# boxer_supply.net
KiCad netlist of a schematic drawn in Altium Designer
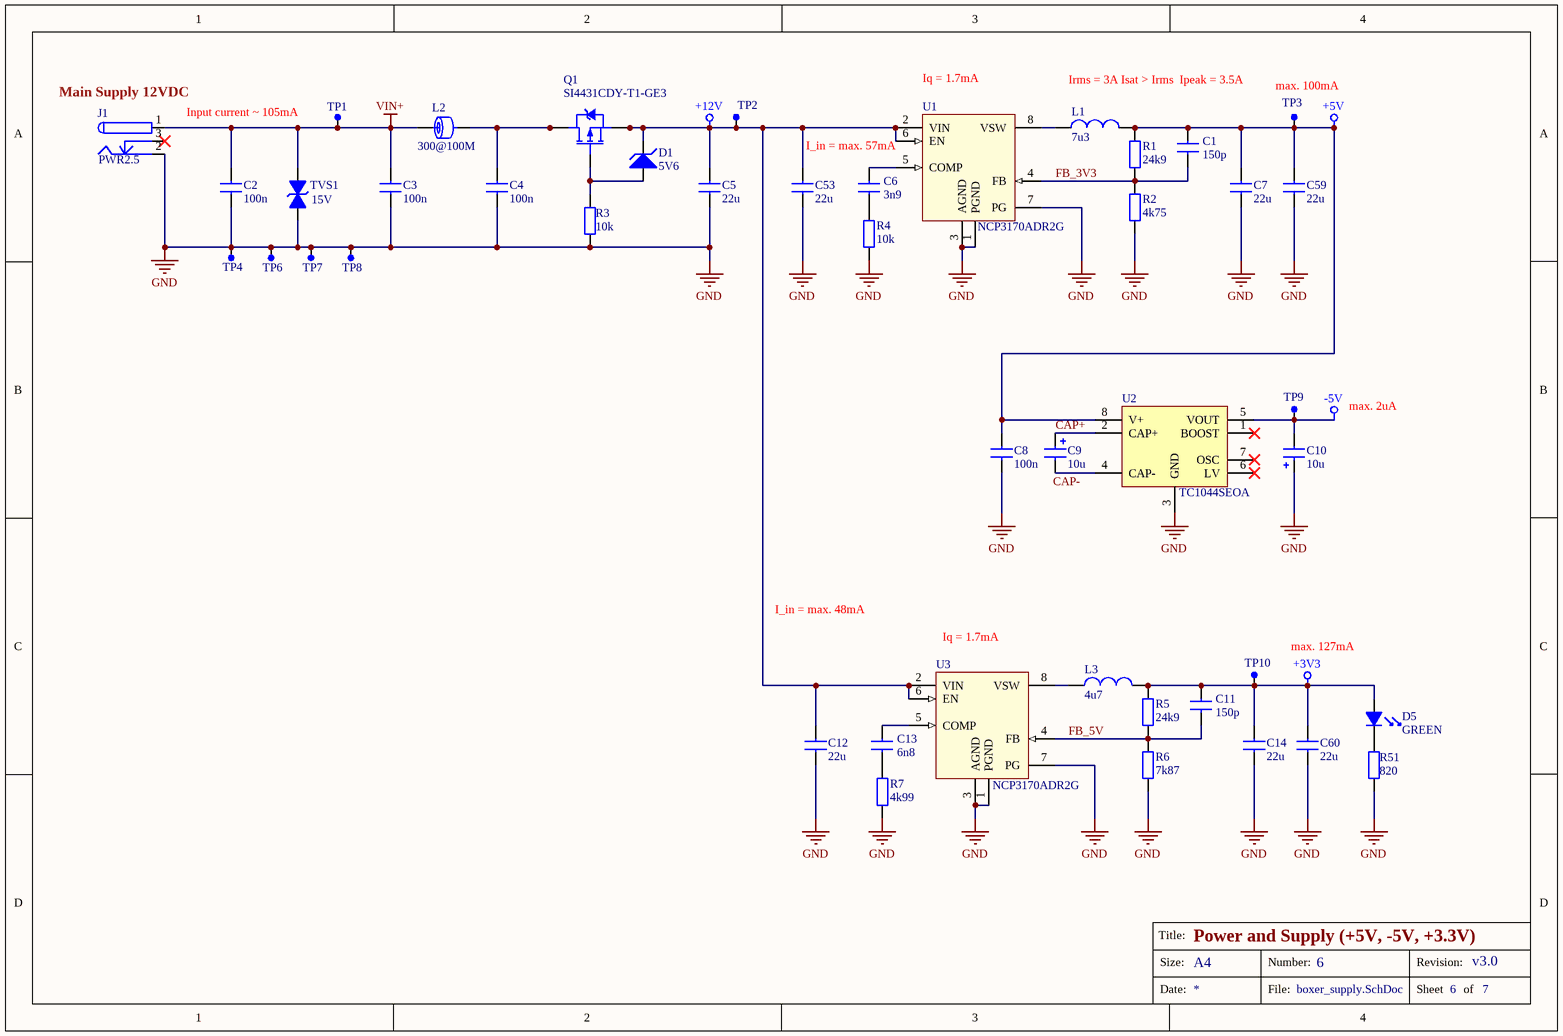
[diagram p0: boxer_supply.SchDoc]

(export (version "E")
  (design (tool "Eeschema 10.0.6"))
  (components
    (comp (ref "C1")
      (value "150p")
      (footprint "C_0805")
      (description "Capacitor")
      (fields (field (name "Comment") "885012207081"))
      (libsource (lib "boxer_pas") (part "Capacitor"))
    )
    (comp (ref "C2")
      (value "100n")
      (footprint "C_0805")
      (description "Capacitor")
      (libsource (lib "boxer_pas") (part "Capacitor"))
    )
    (comp (ref "C3")
      (value "100n")
      (footprint "C_0805")
      (description "Capacitor")
      (libsource (lib "boxer_pas") (part "Capacitor"))
    )
    (comp (ref "C4")
      (value "100n")
      (footprint "C_0805")
      (description "Capacitor")
      (libsource (lib "boxer_pas") (part "Capacitor"))
    )
    (comp (ref "C5")
      (value "22u")
      (footprint "C_1206")
      (description "Capacitor")
      (fields (field (name "Comment") "TME: CL31A226MOCLNNC"))
      (libsource (lib "boxer_pas") (part "Capacitor"))
    )
    (comp (ref "C6")
      (value "3n9")
      (footprint "C_0805")
      (description "Capacitor")
      (fields (field (name "Comment") "885012207089"))
      (libsource (lib "boxer_pas") (part "Capacitor"))
    )
    (comp (ref "C7")
      (value "22u")
      (footprint "C_1206")
      (description "Capacitor")
      (fields (field (name "Comment") "TME: CL31A226MOCLNNC"))
      (libsource (lib "boxer_pas") (part "Capacitor"))
    )
    (comp (ref "C8")
      (value "100n")
      (footprint "C_0805")
      (description "Capacitor")
      (libsource (lib "boxer_pas") (part "Capacitor"))
    )
    (comp (ref "C9")
      (value "10u")
      (footprint "C_SMC")
      (description "Polarized Capacitor")
      (fields (field (name "Comment") "TAJC106K016R"))
      (libsource (lib "boxer_pas") (part "Capacitor Polar"))
    )
    (comp (ref "C10")
      (value "10u")
      (footprint "C_SMC")
      (description "Polarized Capacitor")
      (fields (field (name "Comment") "TAJC106K016R"))
      (libsource (lib "boxer_pas") (part "Capacitor Polar"))
    )
    (comp (ref "C11")
      (value "150p")
      (footprint "C_0805")
      (description "Capacitor")
      (fields (field (name "Comment") "885012207081"))
      (libsource (lib "boxer_pas") (part "Capacitor"))
    )
    (comp (ref "C12")
      (value "22u")
      (footprint "C_1206")
      (description "Capacitor")
      (fields (field (name "Comment") "TME: CL31A226MOCLNNC"))
      (libsource (lib "boxer_pas") (part "Capacitor"))
    )
    (comp (ref "C13")
      (value "6n8")
      (footprint "C_0805")
      (description "Capacitor")
      (fields (field (name "Comment") "885012207091"))
      (libsource (lib "boxer_pas") (part "Capacitor"))
    )
    (comp (ref "C14")
      (value "22u")
      (footprint "C_1206")
      (description "Capacitor")
      (fields (field (name "Comment") "TME: CL31A226MOCLNNC"))
      (libsource (lib "boxer_pas") (part "Capacitor"))
    )
    (comp (ref "C53")
      (value "22u")
      (footprint "C_1206")
      (description "Capacitor")
      (fields (field (name "Comment") "TME: CL31A226MOCLNNC"))
      (libsource (lib "boxer_pas") (part "Capacitor"))
    )
    (comp (ref "C59")
      (value "22u")
      (footprint "C_1206")
      (description "Capacitor")
      (fields (field (name "Comment") "TME: CL31A226MOCLNNC"))
      (libsource (lib "boxer_pas") (part "Capacitor"))
    )
    (comp (ref "C60")
      (value "22u")
      (footprint "C_1206")
      (description "Capacitor")
      (fields (field (name "Comment") "TME: CL31A226MOCLNNC"))
      (libsource (lib "boxer_pas") (part "Capacitor"))
    )
    (comp (ref "D1")
      (value "5V6")
      (footprint "D_SMA")
      (description "Zener Diode")
      (fields (field (name "Comment") "MM3Z5V6B"))
      (libsource (lib "boxer_pas") (part "Diode Zener"))
    )
    (comp (ref "D5")
      (value "GREEN")
      (footprint "LED_0805")
      (description "Typical RED, GREEN, YELLOW, AMBER GaAs LED")
      (fields (field (name "Comment") "KP-2012LSGC"))
      (libsource (lib "altium-import") (part "root_3_LED_"))
    )
    (comp (ref "J1")
      (value "PWR2.5")
      (footprint "WE_WR_DC_694106301002")
      (description "Low Voltage Power Supply Connector")
      (libsource (lib "boxer_mechanical") (part "PWR2.5"))
    )
    (comp (ref "L1")
      (value "7u3")
      (footprint "L_6.7x6.7mm")
      (description "FIXED IND 7.3UH 2.1A 54 MOHM SMD")
      (fields (field (name "Comment") "308-1500-1-ND"))
      (libsource (lib "boxer_pas") (part "Inductor"))
    )
    (comp (ref "L2")
      (value "300@100M")
      (footprint "L_0805")
      (description "Ferrite Bead")
      (fields (field (name "Comment") "742792031"))
      (libsource (lib "boxer_pas") (part "FB"))
    )
    (comp (ref "L3")
      (value "4u7")
      (footprint "L_3.8x3.8mm")
      (description "FIXED IND 4.7UH 1.2A 105 MOHM")
      (fields (field (name "Comment") "732-1008-1-ND"))
      (libsource (lib "boxer_pas") (part "Inductor"))
    )
    (comp (ref "Q1")
      (value "SI4431CDY-T1-GE3")
      (footprint "SO8")
      (description "P-Channel MOSFET")
      (libsource (lib "boxer_pas") (part "MOSFET-P_SO8"))
    )
    (comp (ref "R1")
      (value "24k9")
      (footprint "R_0805")
      (description "Resistor")
      (fields (field (name "Comment") "RNCP0805FTD24K9"))
      (libsource (lib "boxer_pas") (part "Resistor"))
    )
    (comp (ref "R2")
      (value "4k75")
      (footprint "R_0805")
      (description "Resistor")
      (fields (field (name "Comment") "RNCP0805FTD4K75"))
      (libsource (lib "boxer_pas") (part "Resistor"))
    )
    (comp (ref "R3")
      (value "10k")
      (footprint "R_1206")
      (description "Resistor")
      (libsource (lib "boxer_pas") (part "Resistor"))
    )
    (comp (ref "R4")
      (value "10k")
      (footprint "R_1206")
      (description "Resistor")
      (libsource (lib "boxer_pas") (part "Resistor"))
    )
    (comp (ref "R5")
      (value "24k9")
      (footprint "R_0805")
      (description "Resistor")
      (fields (field (name "Comment") "RNCP0805FTD24K9"))
      (libsource (lib "boxer_pas") (part "Resistor"))
    )
    (comp (ref "R6")
      (value "7k87")
      (footprint "R_0805")
      (description "Resistor")
      (fields (field (name "Comment") "RC0805FR-077K87L"))
      (libsource (lib "boxer_pas") (part "Resistor"))
    )
    (comp (ref "R7")
      (value "4k99")
      (footprint "R_0805")
      (description "Resistor")
      (fields (field (name "Comment") "RMCF0805FT4K99"))
      (libsource (lib "boxer_pas") (part "Resistor"))
    )
    (comp (ref "R51")
      (value "820")
      (footprint "R_0805")
      (description "Resistor")
      (libsource (lib "altium-import") (part "root_1_Resistor_"))
    )
    (comp (ref "TP1")
      (value "TEST PAD")
      (footprint "PIN")
      (description "PAD 1.5mm")
      (libsource (lib "boxer_mechanical") (part "TEST_PAD"))
    )
    (comp (ref "TP2")
      (value "TEST PAD")
      (footprint "PIN")
      (description "PAD 1.5mm")
      (libsource (lib "boxer_mechanical") (part "TEST_PAD"))
    )
    (comp (ref "TP3")
      (value "TEST PAD")
      (footprint "PIN")
      (description "PAD 1.5mm")
      (libsource (lib "boxer_mechanical") (part "TEST_PAD"))
    )
    (comp (ref "TP4")
      (value "TEST PAD")
      (footprint "PIN")
      (description "PAD 1.5mm")
      (libsource (lib "boxer_mechanical") (part "TEST_PAD"))
    )
    (comp (ref "TP6")
      (value "TEST PAD")
      (footprint "PIN")
      (description "PAD 1.5mm")
      (libsource (lib "boxer_mechanical") (part "TEST_PAD"))
    )
    (comp (ref "TP7")
      (value "TEST PAD")
      (footprint "PIN")
      (description "PAD 1.5mm")
      (libsource (lib "boxer_mechanical") (part "TEST_PAD"))
    )
    (comp (ref "TP8")
      (value "TEST PAD")
      (footprint "PIN")
      (description "PAD 1.5mm")
      (libsource (lib "boxer_mechanical") (part "TEST_PAD"))
    )
    (comp (ref "TP9")
      (value "TEST PAD")
      (footprint "PIN")
      (description "PAD 1.5mm")
      (libsource (lib "boxer_mechanical") (part "TEST_PAD"))
    )
    (comp (ref "TP10")
      (value "TEST PAD")
      (footprint "PIN")
      (description "PAD 1.5mm")
      (libsource (lib "boxer_mechanical") (part "TEST_PAD"))
    )
    (comp (ref "TVS1")
      (value "15V")
      (footprint "D_SMB")
      (description "Transil")
      (fields (field (name "Comment") "SM6T15CA"))
      (libsource (lib "boxer_pas") (part "Transil"))
    )
    (comp (ref "U1")
      (value "NCP3170ADR2G")
      (footprint "SO8")
      (description "Synchronous PWM Switching Converter")
      (libsource (lib "boxer_ic") (part "NCP3170"))
    )
    (comp (ref "U2")
      (value "TC1044SEOA")
      (footprint "SO8")
      (description "Charge Pump DC-TO-DC Voltage Converter")
      (libsource (lib "boxer_ic") (part "TC1044S"))
    )
    (comp (ref "U3")
      (value "NCP3170ADR2G")
      (footprint "SO8")
      (description "Synchronous PWM Switching Converter")
      (libsource (lib "boxer_ic") (part "NCP3170"))
    )
  )
  (nets
    (net (code "1") (name "+3V3") (class "Default")
      (node (ref "C11") (pin "2") (pinfunction "2_2") (pintype "passive"))
      (node (ref "C14") (pin "2") (pinfunction "2_2") (pintype "passive"))
      (node (ref "C60") (pin "2") (pinfunction "2_2") (pintype "passive"))
      (node (ref "D5") (pin "1") (pinfunction "A_1") (pintype "passive"))
      (node (ref "L3") (pin "2") (pinfunction "2_2") (pintype "passive"))
      (node (ref "R5") (pin "2") (pinfunction "2_2") (pintype "passive"))
      (node (ref "TP10") (pin "1") (pinfunction "1_1") (pintype "passive"))
    )
    (net (code "2") (name "+5V") (class "Default")
      (node (ref "C1") (pin "2") (pinfunction "2_2") (pintype "passive"))
      (node (ref "C59") (pin "2") (pinfunction "2_2") (pintype "passive"))
      (node (ref "C7") (pin "2") (pinfunction "2_2") (pintype "passive"))
      (node (ref "C8") (pin "2") (pinfunction "2_2") (pintype "passive"))
      (node (ref "L1") (pin "2") (pinfunction "2_2") (pintype "passive"))
      (node (ref "R1") (pin "2") (pinfunction "2_2") (pintype "passive"))
      (node (ref "TP3") (pin "1") (pinfunction "1_1") (pintype "passive"))
      (node (ref "U2") (pin "8") (pinfunction "V+_8") (pintype "power_in"))
    )
    (net (code "3") (name "+12V") (class "Default")
      (node (ref "C12") (pin "2") (pinfunction "2_2") (pintype "passive"))
      (node (ref "C5") (pin "2") (pinfunction "2_2") (pintype "passive"))
      (node (ref "C53") (pin "2") (pinfunction "2_2") (pintype "passive"))
      (node (ref "D1") (pin "2") (pinfunction "K_2") (pintype "passive"))
      (node (ref "Q1") (pin "1") (pinfunction "S_1") (pintype "passive"))
      (node (ref "Q1") (pin "2") (pinfunction "S_2") (pintype "passive"))
      (node (ref "Q1") (pin "3") (pinfunction "S_3") (pintype "passive"))
      (node (ref "TP2") (pin "1") (pinfunction "1_1") (pintype "passive"))
      (node (ref "U1") (pin "2") (pinfunction "VIN_2") (pintype "power_in"))
      (node (ref "U1") (pin "6") (pinfunction "EN_6") (pintype "input"))
      (node (ref "U3") (pin "2") (pinfunction "VIN_2") (pintype "power_in"))
      (node (ref "U3") (pin "6") (pinfunction "EN_6") (pintype "input"))
    )
    (net (code "4") (name "-5V") (class "Default")
      (node (ref "C10") (pin "2") (pinfunction "2_2") (pintype "passive"))
      (node (ref "TP9") (pin "1") (pinfunction "1_1") (pintype "passive"))
      (node (ref "U2") (pin "5") (pinfunction "VOUT_5") (pintype "power_in"))
    )
    (net (code "5") (name "/CAP+") (class "Default")
      (node (ref "C9") (pin "1") (pinfunction "1_1") (pintype "passive"))
      (node (ref "U2") (pin "2") (pinfunction "CAP+_2") (pintype "passive"))
    )
    (net (code "6") (name "/CAP-") (class "Default")
      (node (ref "C9") (pin "2") (pinfunction "2_2") (pintype "passive"))
      (node (ref "U2") (pin "4") (pinfunction "CAP-_4") (pintype "passive"))
    )
    (net (code "7") (name "/FB_3V3") (class "Default")
      (node (ref "C1") (pin "1") (pinfunction "1_1") (pintype "passive"))
      (node (ref "R1") (pin "1") (pinfunction "1_1") (pintype "passive"))
      (node (ref "R2") (pin "2") (pinfunction "2_2") (pintype "passive"))
      (node (ref "U1") (pin "4") (pinfunction "FB_4") (pintype "input"))
    )
    (net (code "8") (name "/FB_5V") (class "Default")
      (node (ref "C11") (pin "1") (pinfunction "1_1") (pintype "passive"))
      (node (ref "R5") (pin "1") (pinfunction "1_1") (pintype "passive"))
      (node (ref "R6") (pin "2") (pinfunction "2_2") (pintype "passive"))
      (node (ref "U3") (pin "4") (pinfunction "FB_4") (pintype "input"))
    )
    (net (code "9") (name "GND") (class "Default")
      (node (ref "C10") (pin "1") (pinfunction "1_1") (pintype "passive"))
      (node (ref "C12") (pin "1") (pinfunction "1_1") (pintype "passive"))
      (node (ref "C14") (pin "1") (pinfunction "1_1") (pintype "passive"))
      (node (ref "C2") (pin "1") (pinfunction "1_1") (pintype "passive"))
      (node (ref "C3") (pin "1") (pinfunction "1_1") (pintype "passive"))
      (node (ref "C4") (pin "1") (pinfunction "1_1") (pintype "passive"))
      (node (ref "C5") (pin "1") (pinfunction "1_1") (pintype "passive"))
      (node (ref "C53") (pin "1") (pinfunction "1_1") (pintype "passive"))
      (node (ref "C59") (pin "1") (pinfunction "1_1") (pintype "passive"))
      (node (ref "C60") (pin "1") (pinfunction "1_1") (pintype "passive"))
      (node (ref "C7") (pin "1") (pinfunction "1_1") (pintype "passive"))
      (node (ref "C8") (pin "1") (pinfunction "1_1") (pintype "passive"))
      (node (ref "J1") (pin "2") (pinfunction "2_2") (pintype "power_in"))
      (node (ref "R2") (pin "1") (pinfunction "1_1") (pintype "passive"))
      (node (ref "R3") (pin "1") (pinfunction "1_1") (pintype "passive"))
      (node (ref "R4") (pin "1") (pinfunction "1_1") (pintype "passive"))
      (node (ref "R51") (pin "1") (pinfunction "1_1") (pintype "passive"))
      (node (ref "R6") (pin "1") (pinfunction "1_1") (pintype "passive"))
      (node (ref "R7") (pin "1") (pinfunction "1_1") (pintype "passive"))
      (node (ref "TP4") (pin "1") (pinfunction "1_1") (pintype "passive"))
      (node (ref "TP6") (pin "1") (pinfunction "1_1") (pintype "passive"))
      (node (ref "TP7") (pin "1") (pinfunction "1_1") (pintype "passive"))
      (node (ref "TP8") (pin "1") (pinfunction "1_1") (pintype "passive"))
      (node (ref "TVS1") (pin "1") (pinfunction "A_1") (pintype "passive"))
      (node (ref "U1") (pin "1") (pinfunction "PGND_1") (pintype "power_in"))
      (node (ref "U1") (pin "3") (pinfunction "AGND_3") (pintype "power_in"))
      (node (ref "U1") (pin "7") (pinfunction "PG_7") (pintype "passive"))
      (node (ref "U2") (pin "3") (pinfunction "GND_3") (pintype "power_in"))
      (node (ref "U3") (pin "1") (pinfunction "PGND_1") (pintype "power_in"))
      (node (ref "U3") (pin "3") (pinfunction "AGND_3") (pintype "power_in"))
      (node (ref "U3") (pin "7") (pinfunction "PG_7") (pintype "passive"))
    )
    (net (code "10") (name "Net-(C4-Pad2)") (class "Default")
      (node (ref "C4") (pin "2") (pinfunction "2_2") (pintype "passive"))
      (node (ref "L2") (pin "2") (pinfunction "2_2") (pintype "passive"))
      (node (ref "Q1") (pin "5") (pinfunction "D_5") (pintype "passive"))
      (node (ref "Q1") (pin "6") (pinfunction "D_6") (pintype "passive"))
      (node (ref "Q1") (pin "7") (pinfunction "D_7") (pintype "passive"))
      (node (ref "Q1") (pin "8") (pinfunction "D_8") (pintype "passive"))
    )
    (net (code "11") (name "Net-(C6-Pad1)") (class "Default")
      (node (ref "C6") (pin "1") (pinfunction "1_1") (pintype "passive"))
      (node (ref "R4") (pin "2") (pinfunction "2_2") (pintype "passive"))
    )
    (net (code "12") (name "Net-(C13-Pad1)") (class "Default")
      (node (ref "C13") (pin "1") (pinfunction "1_1") (pintype "passive"))
      (node (ref "R7") (pin "2") (pinfunction "2_2") (pintype "passive"))
    )
    (net (code "13") (name "Net-(D1-A)") (class "Default")
      (node (ref "D1") (pin "1") (pinfunction "A_1") (pintype "passive"))
      (node (ref "Q1") (pin "4") (pinfunction "G_4") (pintype "passive"))
      (node (ref "R3") (pin "2") (pinfunction "2_2") (pintype "passive"))
    )
    (net (code "14") (name "Net-(D5-K)") (class "Default")
      (node (ref "D5") (pin "2") (pinfunction "K_2") (pintype "passive"))
      (node (ref "R51") (pin "2") (pinfunction "2_2") (pintype "passive"))
    )
    (net (code "15") (name "Net-(U1-COMP)") (class "Default")
      (node (ref "C6") (pin "2") (pinfunction "2_2") (pintype "passive"))
      (node (ref "U1") (pin "5") (pinfunction "COMP_5") (pintype "input"))
    )
    (net (code "16") (name "Net-(U1-VSW)") (class "Default")
      (node (ref "L1") (pin "1") (pinfunction "1_1") (pintype "passive"))
      (node (ref "U1") (pin "8") (pinfunction "VSW_8") (pintype "power_in"))
    )
    (net (code "17") (name "Net-(U3-COMP)") (class "Default")
      (node (ref "C13") (pin "2") (pinfunction "2_2") (pintype "passive"))
      (node (ref "U3") (pin "5") (pinfunction "COMP_5") (pintype "input"))
    )
    (net (code "18") (name "Net-(U3-VSW)") (class "Default")
      (node (ref "L3") (pin "1") (pinfunction "1_1") (pintype "passive"))
      (node (ref "U3") (pin "8") (pinfunction "VSW_8") (pintype "power_in"))
    )
    (net (code "19") (name "VIN+") (class "Default")
      (node (ref "C2") (pin "2") (pinfunction "2_2") (pintype "passive"))
      (node (ref "C3") (pin "2") (pinfunction "2_2") (pintype "passive"))
      (node (ref "J1") (pin "1") (pinfunction "1_1") (pintype "power_in"))
      (node (ref "L2") (pin "1") (pinfunction "1_1") (pintype "passive"))
      (node (ref "TP1") (pin "1") (pinfunction "1_1") (pintype "passive"))
      (node (ref "TVS1") (pin "2") (pinfunction "K_2") (pintype "passive"))
    )
    (net (code "20") (name "unconnected-(J1-Pad3)") (class "Default")
      (node (ref "J1") (pin "3") (pinfunction "3_3") (pintype "power_in+no_connect"))
    )
    (net (code "21") (name "unconnected-(U2-BOOST-Pad1)") (class "Default")
      (node (ref "U2") (pin "1") (pinfunction "BOOST_1") (pintype "passive+no_connect"))
    )
    (net (code "22") (name "unconnected-(U2-LV-Pad6)") (class "Default")
      (node (ref "U2") (pin "6") (pinfunction "LV_6") (pintype "passive+no_connect"))
    )
    (net (code "23") (name "unconnected-(U2-OSC-Pad7)") (class "Default")
      (node (ref "U2") (pin "7") (pinfunction "OSC_7") (pintype "passive+no_connect"))
    )
  )
)
